# VibrationACQ.net
KiCad netlist of a schematic drawn in Altium Designer
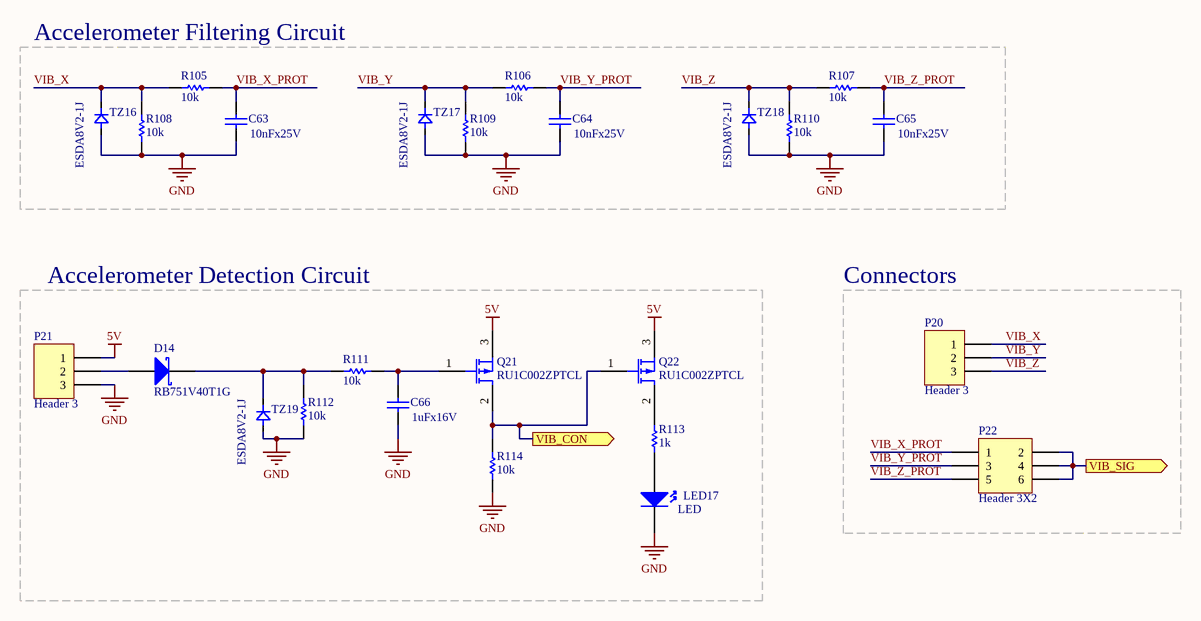
[diagram p0: VibrationACQ.SchDoc]

(export (version "E")
  (design (tool "Eeschema 10.0.6"))
  (components
    (comp (ref "C63")
      (value "10nFx25V")
      (footprint "DISC-0805")
      (description "Capacitor")
      (libsource (lib "IntLib") (part "Cap"))
    )
    (comp (ref "C64")
      (value "10nFx25V")
      (footprint "DISC-0805")
      (description "Capacitor")
      (libsource (lib "IntLib") (part "Cap"))
    )
    (comp (ref "C65")
      (value "10nFx25V")
      (footprint "DISC-0805")
      (description "Capacitor")
      (libsource (lib "IntLib") (part "Cap"))
    )
    (comp (ref "C66")
      (value "1uFx16V")
      (footprint "DISC-0805")
      (description "Capacitor")
      (libsource (lib "IntLib") (part "Cap"))
    )
    (comp (ref "D14")
      (value "RB751V40T1G")
      (footprint "DISC-SOD-323")
      (description "Schottky Diode")
      (fields (field (name "PUBLISHER") "Altium Limited"))
      (libsource (lib "IntLib") (part "D Schottky"))
    )
    (comp (ref "LED17") (value "LED") (footprint "DISC-LED-0.1-PTH") (libsource (lib "IntLib") (part "LED")))
    (comp (ref "P20")
      (value "Header 3")
      (footprint "CON-FLEXWIRE-0.5MM2-1X3")
      (description "Header, 3-Pin")
      (fields (field (name "PUBLISHER") "Altium Limited"))
      (libsource (lib "IntLib") (part "Header 3"))
    )
    (comp (ref "P21")
      (value "Header 3")
      (footprint "CON-FLEXWIRE-0.5MM2-1X3")
      (description "Header, 3-Pin")
      (fields (field (name "PUBLISHER") "Altium Limited"))
      (libsource (lib "IntLib") (part "Header 3"))
    )
    (comp (ref "P22")
      (value "Header 3X2")
      (footprint "CON-HEADER-2X3-PTH")
      (description "Header, 3-Pin, Dual row")
      (fields (field (name "PUBLISHER") "Altium Limited"))
      (libsource (lib "IntLib") (part "Header 3X2"))
    )
    (comp (ref "Q21")
      (value "RU1C002ZPTCL")
      (footprint "DISC-SOT-23")
      (description "P-Channel MOSFET")
      (libsource (lib "IntLib") (part "Transistor-PMOS"))
    )
    (comp (ref "Q22")
      (value "RU1C002ZPTCL")
      (footprint "DISC-SOT-23")
      (description "P-Channel MOSFET")
      (libsource (lib "IntLib") (part "Transistor-PMOS"))
    )
    (comp (ref "R105")
      (value "10k")
      (footprint "DISC-0805")
      (description "Resistor")
      (libsource (lib "IntLib") (part "Res"))
    )
    (comp (ref "R106")
      (value "10k")
      (footprint "DISC-0805")
      (description "Resistor")
      (libsource (lib "IntLib") (part "Res"))
    )
    (comp (ref "R107")
      (value "10k")
      (footprint "DISC-0805")
      (description "Resistor")
      (libsource (lib "IntLib") (part "Res"))
    )
    (comp (ref "R108")
      (value "10k")
      (footprint "DISC-0805")
      (description "Resistor")
      (libsource (lib "IntLib") (part "Res"))
    )
    (comp (ref "R109")
      (value "10k")
      (footprint "DISC-0805")
      (description "Resistor")
      (libsource (lib "IntLib") (part "Res"))
    )
    (comp (ref "R110")
      (value "10k")
      (footprint "DISC-0805")
      (description "Resistor")
      (libsource (lib "IntLib") (part "Res"))
    )
    (comp (ref "R111")
      (value "10k")
      (footprint "DISC-0805")
      (description "Resistor")
      (libsource (lib "IntLib") (part "Res"))
    )
    (comp (ref "R112")
      (value "10k")
      (footprint "DISC-0805")
      (description "Resistor")
      (libsource (lib "IntLib") (part "Res"))
    )
    (comp (ref "R113")
      (value "1k")
      (footprint "DISC-0805")
      (description "Resistor")
      (libsource (lib "IntLib") (part "Res"))
    )
    (comp (ref "R114")
      (value "10k")
      (footprint "DISC-0805")
      (description "Resistor")
      (libsource (lib "IntLib") (part "Res"))
    )
    (comp (ref "TZ16")
      (value "ESDA8V2-1J")
      (footprint "DISC-SOD-323")
      (description "TVZ-Unidirectional")
      (libsource (lib "IntLib") (part "TVZ-Unidirectional"))
    )
    (comp (ref "TZ17")
      (value "ESDA8V2-1J")
      (footprint "DISC-SOD-323")
      (description "TVZ-Unidirectional")
      (libsource (lib "IntLib") (part "TVZ-Unidirectional"))
    )
    (comp (ref "TZ18")
      (value "ESDA8V2-1J")
      (footprint "DISC-SOD-323")
      (description "TVZ-Unidirectional")
      (libsource (lib "IntLib") (part "TVZ-Unidirectional"))
    )
    (comp (ref "TZ19")
      (value "ESDA8V2-1J")
      (footprint "DISC-SOD-323")
      (description "TVZ-Unidirectional")
      (libsource (lib "IntLib") (part "TVZ-Unidirectional"))
    )
  )
  (nets
    (net (code "1") (name "/VIB_CON") (class "Default")
      (node (ref "Q21") (pin "2") (pinfunction "D_2") (pintype "passive"))
      (node (ref "Q22") (pin "1") (pinfunction "G_1") (pintype "passive"))
      (node (ref "R114") (pin "2") (pinfunction "2_2") (pintype "passive"))
    )
    (net (code "2") (name "/VIB_SIG") (class "Default")
      (node (ref "P22") (pin "2") (pinfunction "2_2") (pintype "passive"))
      (node (ref "P22") (pin "4") (pinfunction "4_4") (pintype "passive"))
      (node (ref "P22") (pin "6") (pinfunction "6_6") (pintype "passive"))
    )
    (net (code "3") (name "/VIB_X") (class "Default")
      (node (ref "P20") (pin "1") (pinfunction "1_1") (pintype "passive"))
      (node (ref "R105") (pin "2") (pinfunction "2_2") (pintype "passive"))
      (node (ref "R108") (pin "1") (pinfunction "1_1") (pintype "passive"))
      (node (ref "TZ16") (pin "2") (pinfunction "C_2") (pintype "passive"))
    )
    (net (code "4") (name "/VIB_X_PROT") (class "Default")
      (node (ref "C63") (pin "2") (pinfunction "2_2") (pintype "passive"))
      (node (ref "P22") (pin "1") (pinfunction "1_1") (pintype "passive"))
      (node (ref "R105") (pin "1") (pinfunction "1_1") (pintype "passive"))
    )
    (net (code "5") (name "/VIB_Y") (class "Default")
      (node (ref "P20") (pin "2") (pinfunction "2_2") (pintype "passive"))
      (node (ref "R106") (pin "2") (pinfunction "2_2") (pintype "passive"))
      (node (ref "R109") (pin "1") (pinfunction "1_1") (pintype "passive"))
      (node (ref "TZ17") (pin "2") (pinfunction "C_2") (pintype "passive"))
    )
    (net (code "6") (name "/VIB_Y_PROT") (class "Default")
      (node (ref "C64") (pin "2") (pinfunction "2_2") (pintype "passive"))
      (node (ref "P22") (pin "3") (pinfunction "3_3") (pintype "passive"))
      (node (ref "R106") (pin "1") (pinfunction "1_1") (pintype "passive"))
    )
    (net (code "7") (name "/VIB_Z") (class "Default")
      (node (ref "P20") (pin "3") (pinfunction "3_3") (pintype "passive"))
      (node (ref "R107") (pin "2") (pinfunction "2_2") (pintype "passive"))
      (node (ref "R110") (pin "1") (pinfunction "1_1") (pintype "passive"))
      (node (ref "TZ18") (pin "2") (pinfunction "C_2") (pintype "passive"))
    )
    (net (code "8") (name "/VIB_Z_PROT") (class "Default")
      (node (ref "C65") (pin "2") (pinfunction "2_2") (pintype "passive"))
      (node (ref "P22") (pin "5") (pinfunction "5_5") (pintype "passive"))
      (node (ref "R107") (pin "1") (pinfunction "1_1") (pintype "passive"))
    )
    (net (code "9") (name "5V") (class "Default")
      (node (ref "P21") (pin "1") (pinfunction "1_1") (pintype "passive"))
      (node (ref "Q21") (pin "3") (pinfunction "S_3") (pintype "passive"))
      (node (ref "Q22") (pin "3") (pinfunction "S_3") (pintype "passive"))
    )
    (net (code "10") (name "GND") (class "Default")
      (node (ref "C63") (pin "1") (pinfunction "1_1") (pintype "passive"))
      (node (ref "C64") (pin "1") (pinfunction "1_1") (pintype "passive"))
      (node (ref "C65") (pin "1") (pinfunction "1_1") (pintype "passive"))
      (node (ref "C66") (pin "1") (pinfunction "1_1") (pintype "passive"))
      (node (ref "LED17") (pin "2") (pinfunction "K_2") (pintype "passive"))
      (node (ref "P21") (pin "3") (pinfunction "3_3") (pintype "passive"))
      (node (ref "R108") (pin "2") (pinfunction "2_2") (pintype "passive"))
      (node (ref "R109") (pin "2") (pinfunction "2_2") (pintype "passive"))
      (node (ref "R110") (pin "2") (pinfunction "2_2") (pintype "passive"))
      (node (ref "R112") (pin "2") (pinfunction "2_2") (pintype "passive"))
      (node (ref "R114") (pin "1") (pinfunction "1_1") (pintype "passive"))
      (node (ref "TZ16") (pin "1") (pinfunction "A_1") (pintype "passive"))
      (node (ref "TZ17") (pin "1") (pinfunction "A_1") (pintype "passive"))
      (node (ref "TZ18") (pin "1") (pinfunction "A_1") (pintype "passive"))
      (node (ref "TZ19") (pin "1") (pinfunction "A_1") (pintype "passive"))
    )
    (net (code "11") (name "Net-(D14-A)") (class "Default")
      (node (ref "D14") (pin "1") (pinfunction "A_1") (pintype "passive"))
      (node (ref "P21") (pin "2") (pinfunction "2_2") (pintype "passive"))
    )
    (net (code "12") (name "Net-(D14-K)") (class "Default")
      (node (ref "D14") (pin "2") (pinfunction "K_2") (pintype "passive"))
      (node (ref "R111") (pin "1") (pinfunction "1_1") (pintype "passive"))
      (node (ref "R112") (pin "1") (pinfunction "1_1") (pintype "passive"))
      (node (ref "TZ19") (pin "2") (pinfunction "C_2") (pintype "passive"))
    )
    (net (code "13") (name "Net-(LED17-A)") (class "Default")
      (node (ref "LED17") (pin "1") (pinfunction "A_1") (pintype "passive"))
      (node (ref "R113") (pin "1") (pinfunction "1_1") (pintype "passive"))
    )
    (net (code "14") (name "Net-(Q21-G)") (class "Default")
      (node (ref "C66") (pin "2") (pinfunction "2_2") (pintype "passive"))
      (node (ref "Q21") (pin "1") (pinfunction "G_1") (pintype "passive"))
      (node (ref "R111") (pin "2") (pinfunction "2_2") (pintype "passive"))
    )
    (net (code "15") (name "Net-(Q22-D)") (class "Default")
      (node (ref "Q22") (pin "2") (pinfunction "D_2") (pintype "passive"))
      (node (ref "R113") (pin "2") (pinfunction "2_2") (pintype "passive"))
    )
  )
)
